# BEP3_RPM_BAR_corrected.net
KiCad netlist of a schematic drawn in EAGLE
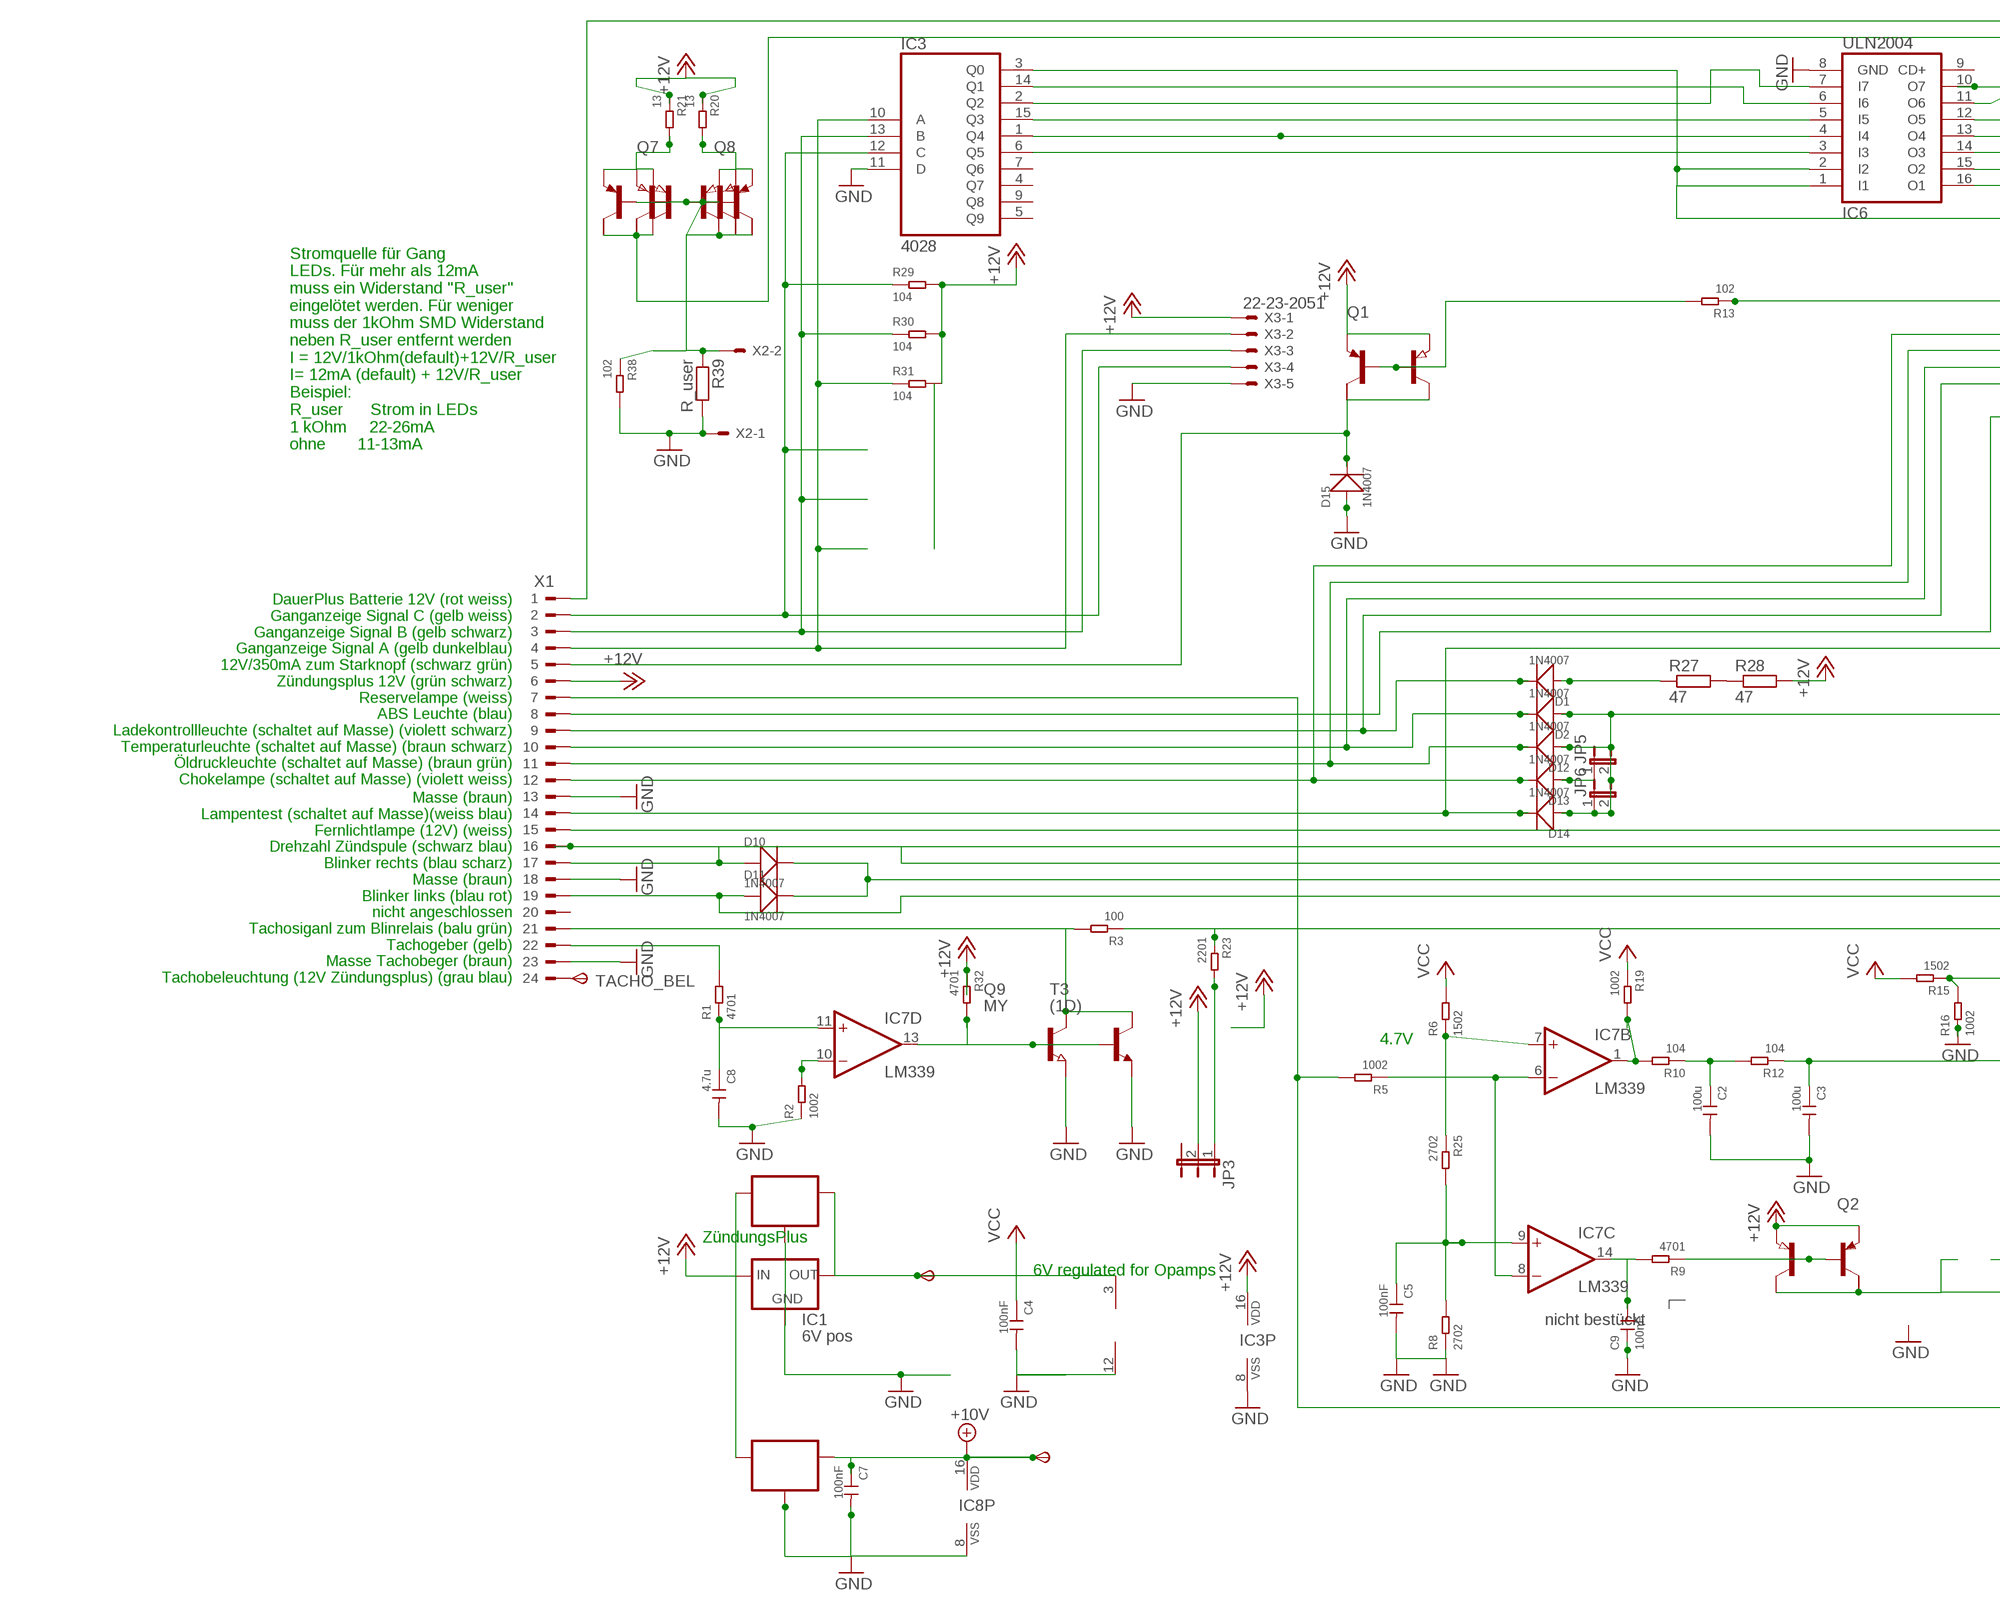
[diagram p0: schematic, sheet 1, part 1 of 2]
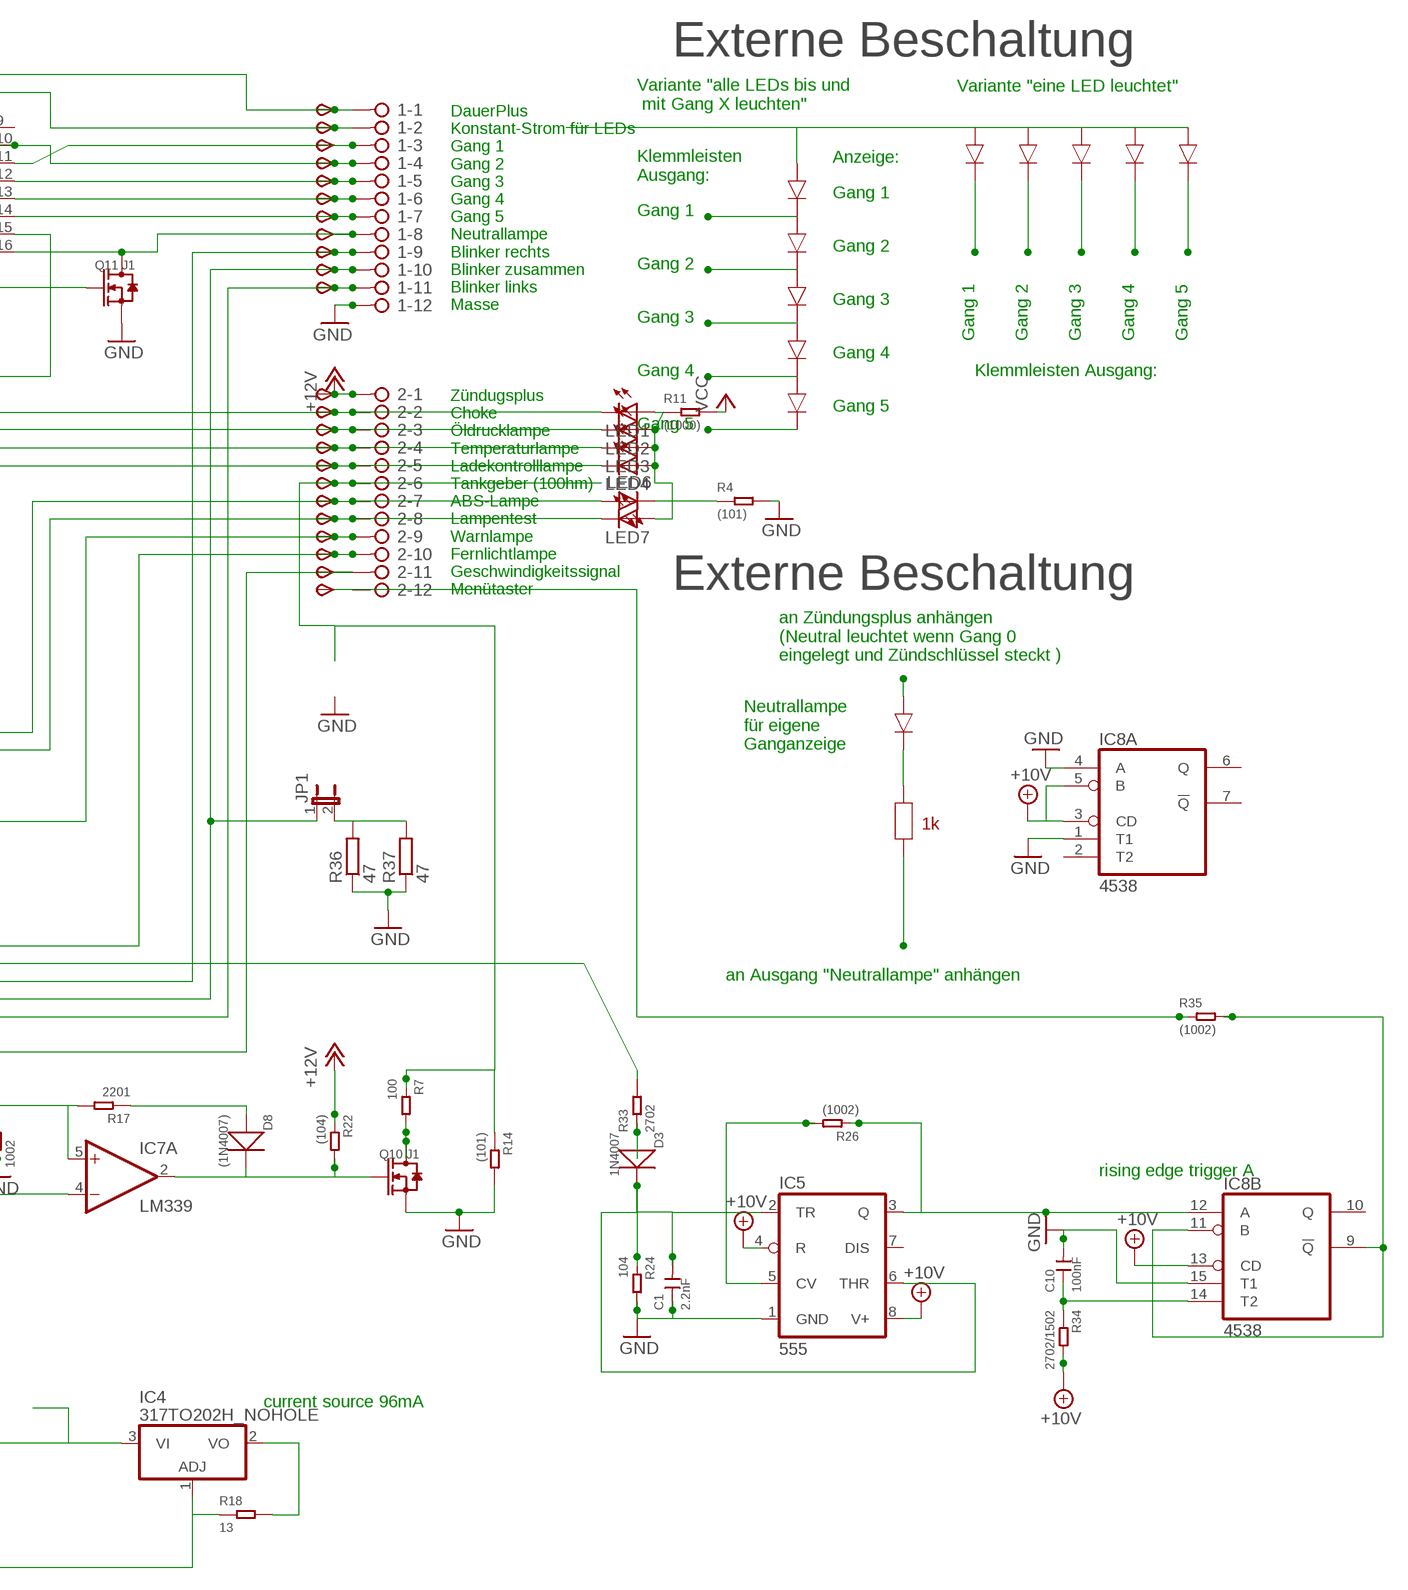
[diagram p1: schematic, sheet 1, part 2 of 2]

(export (version "E")
  (design (tool "Eeschema 10.0.6"))
  (components
    (comp (ref "1")
      (value "2081-1132")
      (footprint "eagle-import:12-PIN")
      (libsource (lib "eagle-import") (part "2081-1132"))
    )
    (comp (ref "2")
      (value "2081-1132")
      (footprint "eagle-import:12-PIN")
      (libsource (lib "eagle-import") (part "2081-1132"))
    )
    (comp (ref "6V")
      (value "TPSB1.8")
      (footprint "eagle-import:B1.8")
      (libsource (lib "eagle-import") (part "TPSB1.8"))
    )
    (comp (ref "10V")
      (value "TPSB1.8")
      (footprint "eagle-import:B1.8")
      (libsource (lib "eagle-import") (part "TPSB1.8"))
    )
    (comp (ref "C1")
      (value "2.2nF")
      (footprint "eagle-import:C0805")
      (fields (field (name "MPN") "CC0805KRX7R9BB104"))
      (libsource (lib "eagle-import") (part "CERAMIC-100NF-50V-10%-X7R(0805)"))
    )
    (comp (ref "C2")
      (value "100u")
      (footprint "eagle-import:C1206")
      (fields (field (name "MPN") "GRM31CR60J107ME39L"))
      (libsource (lib "eagle-import") (part "CERAMIC-100UF-6.3V-20%-X5R(1206)"))
    )
    (comp (ref "C3")
      (value "100u")
      (footprint "eagle-import:C1206")
      (fields (field (name "MPN") "GRM31CR60J107ME39L"))
      (libsource (lib "eagle-import") (part "CERAMIC-100UF-6.3V-20%-X5R(1206)"))
    )
    (comp (ref "C4")
      (value "100nF")
      (footprint "eagle-import:C0805")
      (fields (field (name "MPN") "CC0805KRX7R9BB104"))
      (libsource (lib "eagle-import") (part "CERAMIC-100NF-50V-10%-X7R(0805)"))
    )
    (comp (ref "C5")
      (value "100nF")
      (footprint "eagle-import:C0805")
      (fields (field (name "MPN") "CC0805KRX7R9BB104"))
      (libsource (lib "eagle-import") (part "CERAMIC-100NF-50V-10%-X7R(0805)"))
    )
    (comp (ref "C7")
      (value "100nF")
      (footprint "eagle-import:C0805")
      (fields (field (name "MPN") "CC0805KRX7R9BB104"))
      (libsource (lib "eagle-import") (part "CERAMIC-100NF-50V-10%-X7R(0805)"))
    )
    (comp (ref "C8")
      (value "4.7u")
      (footprint "eagle-import:C0805")
      (fields (field (name "MPN") "CC0805KKX5R8BB475"))
      (libsource (lib "eagle-import") (part "CERAMIC-4.7UF-25V-10%-X5R(0805)"))
    )
    (comp (ref "C9")
      (value "100nF")
      (footprint "eagle-import:C0805")
      (fields (field (name "MPN") "CC0805KRX7R9BB104"))
      (libsource (lib "eagle-import") (part "CERAMIC-100NF-50V-10%-X7R(0805)"))
    )
    (comp (ref "C10")
      (value "100nF")
      (footprint "eagle-import:C0805")
      (fields (field (name "MPN") "CC0805KRX7R9BB104"))
      (libsource (lib "eagle-import") (part "CERAMIC-100NF-50V-10%-X7R(0805)"))
    )
    (comp (ref "D1")
      (value "1N4007")
      (footprint "eagle-import:DO-214AC")
      (libsource (lib "eagle-import") (part "DIODE-GEN-PURPOSE-1KV-1A(DO-214AC)"))
    )
    (comp (ref "D2")
      (value "1N4007")
      (footprint "eagle-import:DO-214AC-1206MOUNT")
      (libsource (lib "eagle-import") (part "DIODE-GEN-PURPOSE-1KV-1A(DO-214AC)DO-214AC/1206"))
    )
    (comp (ref "D3")
      (value "1N4007")
      (footprint "eagle-import:DO-214AC")
      (libsource (lib "eagle-import") (part "DIODE-GEN-PURPOSE-1KV-1A(DO-214AC)"))
    )
    (comp (ref "D8")
      (value "(1N4007)")
      (footprint "eagle-import:DO-214AC-1206MOUNT")
      (libsource (lib "eagle-import") (part "DIODE-GEN-PURPOSE-1KV-1A(DO-214AC)DO-214AC/1206"))
    )
    (comp (ref "D10")
      (value "1N4007")
      (footprint "eagle-import:DO-214AC")
      (libsource (lib "eagle-import") (part "DIODE-GEN-PURPOSE-1KV-1A(DO-214AC)"))
    )
    (comp (ref "D11")
      (value "1N4007")
      (footprint "eagle-import:DO-214AC")
      (libsource (lib "eagle-import") (part "DIODE-GEN-PURPOSE-1KV-1A(DO-214AC)"))
    )
    (comp (ref "D12")
      (value "1N4007")
      (footprint "eagle-import:DO-214AC-1206MOUNT")
      (libsource (lib "eagle-import") (part "DIODE-GEN-PURPOSE-1KV-1A(DO-214AC)DO-214AC/1206"))
    )
    (comp (ref "D13")
      (value "1N4007")
      (footprint "eagle-import:DO-214AC-1206MOUNT")
      (libsource (lib "eagle-import") (part "DIODE-GEN-PURPOSE-1KV-1A(DO-214AC)DO-214AC/1206"))
    )
    (comp (ref "D14")
      (value "1N4007")
      (footprint "eagle-import:DO-214AC-1206MOUNT")
      (libsource (lib "eagle-import") (part "DIODE-GEN-PURPOSE-1KV-1A(DO-214AC)DO-214AC/1206"))
    )
    (comp (ref "D15")
      (value "1N4007")
      (footprint "eagle-import:DO-214AC")
      (libsource (lib "eagle-import") (part "DIODE-GEN-PURPOSE-1KV-1A(DO-214AC)"))
    )
    (comp (ref "IC1")
      (value "6V pos")
      (footprint "eagle-import:78LXX")
      (libsource (lib "eagle-import") (part "v-reg_78LXX"))
    )
    (comp (ref "IC2")
      (value "78LXXSOT89_ROUND")
      (footprint "eagle-import:SOT89_ROUND")
      (libsource (lib "eagle-import") (part "78LXXSOT89_ROUND"))
    )
    (comp (ref "IC3")
      (value "4028")
      (footprint "eagle-import:SO16")
      (libsource (lib "eagle-import") (part "4028D"))
    )
    (comp (ref "IC4")
      (value "317TO202H_NOHOLE")
      (footprint "eagle-import:TO220H_NOHOLE")
      (libsource (lib "eagle-import") (part "317TO202H_NOHOLE"))
    )
    (comp (ref "IC5")
      (value "555")
      (footprint "eagle-import:SO08")
      (libsource (lib "eagle-import") (part "555DNE"))
    )
    (comp (ref "IC6")
      (value "ULN2004")
      (footprint "eagle-import:SO16")
      (libsource (lib "eagle-import") (part "ULN2004AD"))
    )
    (comp (ref "IC7")
      (value "LM339")
      (footprint "eagle-import:SO14")
      (libsource (lib "eagle-import") (part "LM339D"))
    )
    (comp (ref "IC8")
      (value "4538")
      (footprint "eagle-import:SO16")
      (libsource (lib "eagle-import") (part "4538D"))
    )
    (comp (ref "IC9")
      (value "78LXXSOT89_ROUND")
      (footprint "eagle-import:SOT89_ROUND")
      (libsource (lib "eagle-import") (part "78LXXSOT89_ROUND"))
    )
    (comp (ref "JP1")
      (value "JP1E")
      (footprint "eagle-import:JP1")
      (libsource (lib "eagle-import") (part "JP1E"))
    )
    (comp (ref "JP3")
      (value "JP2E")
      (footprint "eagle-import:JP2")
      (libsource (lib "eagle-import") (part "JP2E"))
    )
    (comp (ref "JP5")
      (value "JP1E")
      (footprint "eagle-import:JP1")
      (libsource (lib "eagle-import") (part "JP1E"))
    )
    (comp (ref "JP6")
      (value "JP1E")
      (footprint "eagle-import:JP1")
      (libsource (lib "eagle-import") (part "JP1E"))
    )
    (comp (ref "LED1")
      (value "LEDLD260")
      (footprint "eagle-import:LD260")
      (libsource (lib "eagle-import") (part "LEDLD260"))
    )
    (comp (ref "LED2")
      (value "LEDLD260")
      (footprint "eagle-import:LD260")
      (libsource (lib "eagle-import") (part "LEDLD260"))
    )
    (comp (ref "LED3")
      (value "LEDLD260")
      (footprint "eagle-import:LD260")
      (libsource (lib "eagle-import") (part "LEDLD260"))
    )
    (comp (ref "LED4")
      (value "LEDLD260")
      (footprint "eagle-import:LD260")
      (libsource (lib "eagle-import") (part "LEDLD260"))
    )
    (comp (ref "LED6")
      (value "LEDLD260")
      (footprint "eagle-import:LD260")
      (libsource (lib "eagle-import") (part "LEDLD260"))
    )
    (comp (ref "LED7")
      (value "LEDLD260")
      (footprint "eagle-import:LD260")
      (libsource (lib "eagle-import") (part "LEDLD260"))
    )
    (comp (ref "Q1")
      (value "PNP-TRANSISTOR_SOT89")
      (footprint "eagle-import:SOT89")
      (libsource (lib "eagle-import") (part "PNP-TRANSISTOR_SOT89"))
    )
    (comp (ref "Q2")
      (value "PNP-TRANSISTOR_SOT89")
      (footprint "eagle-import:SOT89")
      (libsource (lib "eagle-import") (part "PNP-TRANSISTOR_SOT89"))
    )
    (comp (ref "Q3")
      (value "AH-16")
      (footprint "eagle-import:SOT223")
      (libsource (lib "eagle-import") (part "BCP53T1"))
    )
    (comp (ref "Q4")
      (value "(AH-16)")
      (footprint "eagle-import:SOT223")
      (libsource (lib "eagle-import") (part "BCP53T1"))
    )
    (comp (ref "Q5")
      (value "(AH-16)")
      (footprint "eagle-import:SOT223")
      (libsource (lib "eagle-import") (part "BCP53T1"))
    )
    (comp (ref "Q6")
      (value "(AH-16)")
      (footprint "eagle-import:SOT223")
      (libsource (lib "eagle-import") (part "BCP53T1"))
    )
    (comp (ref "Q7")
      (value "PNP-TRANSISTOR_SOT89")
      (footprint "eagle-import:SOT89")
      (libsource (lib "eagle-import") (part "PNP-TRANSISTOR_SOT89"))
    )
    (comp (ref "Q8")
      (value "PNP-TRANSISTOR_SOT89")
      (footprint "eagle-import:SOT89")
      (libsource (lib "eagle-import") (part "PNP-TRANSISTOR_SOT89"))
    )
    (comp (ref "Q9")
      (value "MY")
      (footprint "eagle-import:SOT89")
      (libsource (lib "eagle-import") (part "NPN-TRANSISTOR_SOT89"))
    )
    (comp (ref "Q10")
      (value "J1")
      (footprint "eagle-import:SOT-23")
      (fields (field (name "MPN") "BSS138W-7-F"))
      (libsource (lib "eagle-import") (part "SMD-MOSFET-N-CH-50V-200MA-BSS138W-7-F(SOT-23)"))
    )
    (comp (ref "Q11")
      (value "J1")
      (footprint "eagle-import:SOT-23")
      (fields (field (name "MPN") "BSS138W-7-F"))
      (libsource (lib "eagle-import") (part "SMD-MOSFET-N-CH-50V-200MA-BSS138W-7-F(SOT-23)"))
    )
    (comp (ref "R1")
      (value "4701")
      (footprint "eagle-import:R0805")
      (fields (field (name "MPN") "RC0805JR-074K7L"))
      (libsource (lib "eagle-import") (part "SMD-RES-4.7K-5%-1/8W(0805)"))
    )
    (comp (ref "R2")
      (value "1002")
      (footprint "eagle-import:R0805")
      (fields (field (name "MPN") "RC0805FR-0710KL"))
      (libsource (lib "eagle-import") (part "SMD-RES-10K-1%-1/8W(0805)"))
    )
    (comp (ref "R3")
      (value "100")
      (footprint "eagle-import:R0805")
      (fields (field (name "MPN") "RC0805JR-07220RL"))
      (libsource (lib "eagle-import") (part "SMD-RES-220R-5%-1/8W(0805)"))
    )
    (comp (ref "R4")
      (value "(101)")
      (footprint "eagle-import:R0805")
      (fields (field (name "MPN") "RC0805JR-07100RL"))
      (libsource (lib "eagle-import") (part "SMD-RES-100R-5%-1/8W(0805)"))
    )
    (comp (ref "R5")
      (value "1002")
      (footprint "eagle-import:R0805")
      (fields (field (name "MPN") "RC0805FR-0710KL"))
      (libsource (lib "eagle-import") (part "SMD-RES-10K-1%-1/8W(0805)"))
    )
    (comp (ref "R6")
      (value "1502")
      (footprint "eagle-import:R0805")
      (fields (field (name "MPN") "RC0805FR-0710KL"))
      (libsource (lib "eagle-import") (part "SMD-RES-10K-1%-1/8W(0805)"))
    )
    (comp (ref "R7")
      (value "100")
      (footprint "eagle-import:R0805")
      (fields (field (name "MPN") "RC0805JR-072K2L"))
      (libsource (lib "eagle-import") (part "SMD-RES-2.2K-5%-1/8W(0805)"))
    )
    (comp (ref "R8")
      (value "2702")
      (footprint "eagle-import:R0805")
      (fields (field (name "MPN") "RC0805JR-074K7L"))
      (libsource (lib "eagle-import") (part "SMD-RES-4.7K-5%-1/8W(0805)"))
    )
    (comp (ref "R9")
      (value "4701")
      (footprint "eagle-import:R0805")
      (fields (field (name "MPN") "RC0805JR-074K7L"))
      (libsource (lib "eagle-import") (part "SMD-RES-4.7K-5%-1/8W(0805)"))
    )
    (comp (ref "R10")
      (value "104")
      (footprint "eagle-import:R0805")
      (fields (field (name "MPN") "RC0805FR-0710KL"))
      (libsource (lib "eagle-import") (part "SMD-RES-10K-1%-1/8W(0805)"))
    )
    (comp (ref "R11")
      (value "(1000)")
      (footprint "eagle-import:R0805")
      (fields (field (name "MPN") "RC0805JR-07100RL"))
      (libsource (lib "eagle-import") (part "SMD-RES-100R-5%-1/8W(0805)"))
    )
    (comp (ref "R12")
      (value "104")
      (footprint "eagle-import:R0805")
      (fields (field (name "MPN") "RC0805FR-0710KL"))
      (libsource (lib "eagle-import") (part "SMD-RES-10K-1%-1/8W(0805)"))
    )
    (comp (ref "R13")
      (value "102")
      (footprint "eagle-import:R0805")
      (fields (field (name "MPN") "RC0805JR-071KL"))
      (libsource (lib "eagle-import") (part "SMD-RES-1K-5%-1/8W(0805)"))
    )
    (comp (ref "R14")
      (value "(101)")
      (footprint "eagle-import:R0805")
      (fields (field (name "MPN") "RC0805JR-072K2L"))
      (libsource (lib "eagle-import") (part "SMD-RES-2.2K-5%-1/8W(0805)"))
    )
    (comp (ref "R15")
      (value "1502")
      (footprint "eagle-import:R0805")
      (fields (field (name "MPN") "RC0805FR-0710KL"))
      (libsource (lib "eagle-import") (part "SMD-RES-10K-1%-1/8W(0805)"))
    )
    (comp (ref "R16")
      (value "1002")
      (footprint "eagle-import:R0805")
      (fields (field (name "MPN") "RC0805FR-0710KL"))
      (libsource (lib "eagle-import") (part "SMD-RES-10K-1%-1/8W(0805)"))
    )
    (comp (ref "R17")
      (value "2201")
      (footprint "eagle-import:R0805")
      (fields (field (name "MPN") "RC0805JR-072K2L"))
      (libsource (lib "eagle-import") (part "SMD-RES-2.2K-5%-1/8W(0805)"))
    )
    (comp (ref "R18")
      (value "13")
      (footprint "eagle-import:R1206")
      (fields (field (name "MPN") "RC1206JR-0713RL"))
      (libsource (lib "eagle-import") (part "SMD-RES-13R-5%-1/4W(1206)"))
    )
    (comp (ref "R19")
      (value "1002")
      (footprint "eagle-import:R0805")
      (fields (field (name "MPN") "RC0805FR-0710KL"))
      (libsource (lib "eagle-import") (part "SMD-RES-10K-1%-1/8W(0805)"))
    )
    (comp (ref "R20")
      (value "13")
      (footprint "eagle-import:R1206")
      (fields (field (name "MPN") "RC1206JR-0713RL"))
      (libsource (lib "eagle-import") (part "SMD-RES-13R-5%-1/4W(1206)"))
    )
    (comp (ref "R21")
      (value "13")
      (footprint "eagle-import:R1206")
      (fields (field (name "MPN") "RC1206JR-0713RL"))
      (libsource (lib "eagle-import") (part "SMD-RES-13R-5%-1/4W(1206)"))
    )
    (comp (ref "R22")
      (value "(104)")
      (footprint "eagle-import:R0805")
      (fields (field (name "MPN") "RC0805FR-0710KL"))
      (libsource (lib "eagle-import") (part "SMD-RES-10K-1%-1/8W(0805)"))
    )
    (comp (ref "R23")
      (value "2201")
      (footprint "eagle-import:R0805")
      (fields (field (name "MPN") "RC0805JR-072K2L"))
      (libsource (lib "eagle-import") (part "SMD-RES-2.2K-5%-1/8W(0805)"))
    )
    (comp (ref "R24")
      (value "104")
      (footprint "eagle-import:R0805")
      (fields (field (name "MPN") "RC0805FR-0710KL"))
      (libsource (lib "eagle-import") (part "SMD-RES-10K-1%-1/8W(0805)"))
    )
    (comp (ref "R25")
      (value "2702")
      (footprint "eagle-import:R0805")
      (fields (field (name "MPN") "RC0805JR-074K7L"))
      (libsource (lib "eagle-import") (part "SMD-RES-4.7K-5%-1/8W(0805)"))
    )
    (comp (ref "R26")
      (value "(1002)")
      (footprint "eagle-import:R0805")
      (fields (field (name "MPN") "RC0805FR-0710KL"))
      (libsource (lib "eagle-import") (part "SMD-RES-10K-1%-1/8W(0805)"))
    )
    (comp (ref "R27")
      (value "47")
      (footprint "eagle-import:V235_17_1MM")
      (libsource (lib "eagle-import") (part "R-EU_V235/17_1MM"))
    )
    (comp (ref "R28")
      (value "47")
      (footprint "eagle-import:V235_17_1MM")
      (libsource (lib "eagle-import") (part "R-EU_V235/17_1MM"))
    )
    (comp (ref "R29")
      (value "104")
      (footprint "eagle-import:R0805")
      (fields (field (name "MPN") "RC0805FR-0710KL"))
      (libsource (lib "eagle-import") (part "SMD-RES-10K-1%-1/8W(0805)"))
    )
    (comp (ref "R30")
      (value "104")
      (footprint "eagle-import:R0805")
      (fields (field (name "MPN") "RC0805FR-0710KL"))
      (libsource (lib "eagle-import") (part "SMD-RES-10K-1%-1/8W(0805)"))
    )
    (comp (ref "R31")
      (value "104")
      (footprint "eagle-import:R0805")
      (fields (field (name "MPN") "RC0805FR-0710KL"))
      (libsource (lib "eagle-import") (part "SMD-RES-10K-1%-1/8W(0805)"))
    )
    (comp (ref "R32")
      (value "4701")
      (footprint "eagle-import:R0805")
      (fields (field (name "MPN") "RC0805JR-074K7L"))
      (libsource (lib "eagle-import") (part "SMD-RES-4.7K-5%-1/8W(0805)"))
    )
    (comp (ref "R33")
      (value "2702")
      (footprint "eagle-import:R0805")
      (fields (field (name "MPN") "RC0805FR-0710KL"))
      (libsource (lib "eagle-import") (part "SMD-RES-10K-1%-1/8W(0805)"))
    )
    (comp (ref "R34")
      (value "2702/1502")
      (footprint "eagle-import:R0805")
      (fields (field (name "MPN") "RC0805JR-074K7L"))
      (libsource (lib "eagle-import") (part "SMD-RES-4.7K-5%-1/8W(0805)"))
    )
    (comp (ref "R35")
      (value "(1002)")
      (footprint "eagle-import:R0805")
      (fields (field (name "MPN") "RC0805JR-074K7L"))
      (libsource (lib "eagle-import") (part "SMD-RES-4.7K-5%-1/8W(0805)"))
    )
    (comp (ref "R36")
      (value "47")
      (footprint "eagle-import:V235_17_1MM")
      (libsource (lib "eagle-import") (part "R-EU_V235/17_1MM"))
    )
    (comp (ref "R37")
      (value "47")
      (footprint "eagle-import:V235_17_1MM")
      (libsource (lib "eagle-import") (part "R-EU_V235/17_1MM"))
    )
    (comp (ref "R38")
      (value "102")
      (footprint "eagle-import:R0805")
      (fields (field (name "MPN") "RC0805JR-071KL"))
      (libsource (lib "eagle-import") (part "SMD-RES-1K-5%-1/8W(0805)"))
    )
    (comp (ref "R39")
      (value "R_user")
      (footprint "eagle-import:R0805")
      (libsource (lib "eagle-import") (part "R-EU_R0805"))
    )
    (comp (ref "T1")
      (value "PNP2SM8")
      (footprint "eagle-import:SM8")
      (libsource (lib "eagle-import") (part "PNP2SM8"))
    )
    (comp (ref "T3")
      (value "(1D)")
      (footprint "eagle-import:SOT23-BEC")
      (libsource (lib "eagle-import") (part "-NPN-SOT23-BECMMBTA42LT1"))
    )
    (comp (ref "TACHO_BEL")
      (value "TPSP1_1MM")
      (footprint "eagle-import:P1_1.0MM")
      (libsource (lib "eagle-import") (part "TPSP1_1MM"))
    )
    (comp (ref "TP1")
      (value "TPSB1.8")
      (footprint "eagle-import:B1.8")
      (libsource (lib "eagle-import") (part "TPSB1.8"))
    )
    (comp (ref "TP2")
      (value "TPSB1.8")
      (footprint "eagle-import:B1.8")
      (libsource (lib "eagle-import") (part "TPSB1.8"))
    )
    (comp (ref "TP3")
      (value "TPSB1.8")
      (footprint "eagle-import:B1.8")
      (libsource (lib "eagle-import") (part "TPSB1.8"))
    )
    (comp (ref "TP4")
      (value "TPSB1.8")
      (footprint "eagle-import:B1.8")
      (libsource (lib "eagle-import") (part "TPSB1.8"))
    )
    (comp (ref "TP5")
      (value "TPSB1.8")
      (footprint "eagle-import:B1.8")
      (libsource (lib "eagle-import") (part "TPSB1.8"))
    )
    (comp (ref "TP6")
      (value "TPSB1.8")
      (footprint "eagle-import:B1.8")
      (libsource (lib "eagle-import") (part "TPSB1.8"))
    )
    (comp (ref "TP7")
      (value "TPSB1.8")
      (footprint "eagle-import:B1.8")
      (libsource (lib "eagle-import") (part "TPSB1.8"))
    )
    (comp (ref "TP8")
      (value "TPSB1.8")
      (footprint "eagle-import:B1.8")
      (libsource (lib "eagle-import") (part "TPSB1.8"))
    )
    (comp (ref "TP9")
      (value "TPSB1.8")
      (footprint "eagle-import:B1.8")
      (libsource (lib "eagle-import") (part "TPSB1.8"))
    )
    (comp (ref "TP10")
      (value "TPSB1.8")
      (footprint "eagle-import:B1.8")
      (libsource (lib "eagle-import") (part "TPSB1.8"))
    )
    (comp (ref "TP11")
      (value "TPSB1.8")
      (footprint "eagle-import:B1.8")
      (libsource (lib "eagle-import") (part "TPSB1.8"))
    )
    (comp (ref "TP12")
      (value "TPSB1.8")
      (footprint "eagle-import:B1.8")
      (libsource (lib "eagle-import") (part "TPSB1.8"))
    )
    (comp (ref "TP13")
      (value "TPSB1,27")
      (footprint "eagle-import:B1,27")
      (libsource (lib "eagle-import") (part "TPSB1,27"))
    )
    (comp (ref "TP16")
      (value "TPSB1.8")
      (footprint "eagle-import:B1.8")
      (libsource (lib "eagle-import") (part "TPSB1.8"))
    )
    (comp (ref "TP17")
      (value "TPSB1.8")
      (footprint "eagle-import:B1.8")
      (libsource (lib "eagle-import") (part "TPSB1.8"))
    )
    (comp (ref "TP18")
      (value "TPSB1.8")
      (footprint "eagle-import:B1.8")
      (libsource (lib "eagle-import") (part "TPSB1.8"))
    )
    (comp (ref "TP19")
      (value "TPSB1.8")
      (footprint "eagle-import:B1.8")
      (libsource (lib "eagle-import") (part "TPSB1.8"))
    )
    (comp (ref "TP21")
      (value "TPSB1.8")
      (footprint "eagle-import:B1.8")
      (libsource (lib "eagle-import") (part "TPSB1.8"))
    )
    (comp (ref "TP22")
      (value "TPSB1.8")
      (footprint "eagle-import:B1.8")
      (libsource (lib "eagle-import") (part "TPSB1.8"))
    )
    (comp (ref "TP23")
      (value "TPSB1.8")
      (footprint "eagle-import:B1.8")
      (libsource (lib "eagle-import") (part "TPSB1.8"))
    )
    (comp (ref "TP24")
      (value "TPSB1,27")
      (footprint "eagle-import:B1,27")
      (libsource (lib "eagle-import") (part "TPSB1,27"))
    )
    (comp (ref "TP25")
      (value "TPSB1.8")
      (footprint "eagle-import:B1.8")
      (libsource (lib "eagle-import") (part "TPSB1.8"))
    )
    (comp (ref "TP26")
      (value "TPSB1.8")
      (footprint "eagle-import:B1.8")
      (libsource (lib "eagle-import") (part "TPSB1.8"))
    )
    (comp (ref "X1")
      (value "CON_BMWV2")
      (footprint "eagle-import:24-PIN_V2")
      (libsource (lib "eagle-import") (part "CON_BMWV2"))
    )
    (comp (ref "X2")
      (value "22-23-2021")
      (footprint "eagle-import:22-23-2021")
      (fields (field (name "MF") "MOLEX"))
      (libsource (lib "eagle-import") (part "22-23-2021"))
    )
    (comp (ref "X3")
      (value "22-23-2051")
      (footprint "eagle-import:22-23-2051")
      (fields (field (name "MF") "MOLEX"))
      (libsource (lib "eagle-import") (part "22-23-2051"))
    )
  )
  (nets
    (net (code "1") (name "+10V") (class "Default")
      (node (ref "10V") (pin "TP") (pinfunction "PP_TP") (pintype "input"))
      (node (ref "C7") (pin "1") (pinfunction "1_1") (pintype "passive"))
      (node (ref "IC5") (pin "4") (pinfunction "R_4") (pintype "input"))
      (node (ref "IC5") (pin "8") (pinfunction "V+_8") (pintype "power_in"))
      (node (ref "IC8") (pin "13") (pinfunction "CD_13") (pintype "input"))
      (node (ref "IC8") (pin "16") (pinfunction "VDD_16") (pintype "power_in"))
      (node (ref "IC8") (pin "3") (pinfunction "CD_3") (pintype "input"))
      (node (ref "IC8") (pin "5") (pinfunction "B_5") (pintype "input"))
      (node (ref "IC9") (pin "1") (pinfunction "OUT_1") (pintype "passive"))
      (node (ref "R34") (pin "2") (pinfunction "2_2") (pintype "passive"))
    )
    (net (code "2") (name "+12V") (class "Default")
      (node (ref "2") (pin "1") (pinfunction "KL_1") (pintype "passive"))
      (node (ref "IC1") (pin "IN") (pinfunction "IN_IN") (pintype "input"))
      (node (ref "IC2") (pin "3") (pinfunction "IN_3") (pintype "input"))
      (node (ref "IC3") (pin "16") (pinfunction "VDD_16") (pintype "power_in"))
      (node (ref "IC9") (pin "3") (pinfunction "IN_3") (pintype "input"))
      (node (ref "JP3") (pin "2") (pinfunction "2_2") (pintype "passive"))
      (node (ref "Q1") (pin "3") (pinfunction "E_3") (pintype "passive"))
      (node (ref "Q2") (pin "3") (pinfunction "E_3") (pintype "passive"))
      (node (ref "Q3") (pin "3") (pinfunction "E_3") (pintype "passive"))
      (node (ref "Q4") (pin "3") (pinfunction "E_3") (pintype "passive"))
      (node (ref "R20") (pin "1") (pinfunction "1_1") (pintype "passive"))
      (node (ref "R21") (pin "1") (pinfunction "1_1") (pintype "passive"))
      (node (ref "R22") (pin "1") (pinfunction "1_1") (pintype "passive"))
      (node (ref "R28") (pin "2") (pinfunction "2_2") (pintype "passive"))
      (node (ref "R29") (pin "2") (pinfunction "2_2") (pintype "passive"))
      (node (ref "R30") (pin "2") (pinfunction "2_2") (pintype "passive"))
      (node (ref "R31") (pin "2") (pinfunction "2_2") (pintype "passive"))
      (node (ref "R32") (pin "1") (pinfunction "1_1") (pintype "passive"))
      (node (ref "TP12") (pin "TP") (pinfunction "PP_TP") (pintype "input"))
      (node (ref "X1") (pin "6") (pinfunction "6_6") (pintype "passive"))
      (node (ref "X3") (pin "1") (pinfunction "S_1") (pintype "passive"))
    )
    (net (code "3") (name "GND") (class "Default")
      (node (ref "1") (pin "12") (pinfunction "KL_12") (pintype "passive"))
      (node (ref "C1") (pin "1") (pinfunction "1_1") (pintype "passive"))
      (node (ref "C10") (pin "2") (pinfunction "2_2") (pintype "passive"))
      (node (ref "C2") (pin "2") (pinfunction "2_2") (pintype "passive"))
      (node (ref "C3") (pin "2") (pinfunction "2_2") (pintype "passive"))
      (node (ref "C4") (pin "2") (pinfunction "2_2") (pintype "passive"))
      (node (ref "C5") (pin "2") (pinfunction "2_2") (pintype "passive"))
      (node (ref "C7") (pin "2") (pinfunction "2_2") (pintype "passive"))
      (node (ref "C8") (pin "2") (pinfunction "2_2") (pintype "passive"))
      (node (ref "C9") (pin "1") (pinfunction "1_1") (pintype "passive"))
      (node (ref "D15") (pin "1") (pinfunction "+_1") (pintype "passive"))
      (node (ref "IC1") (pin "GND") (pinfunction "GND_GND") (pintype "input"))
      (node (ref "IC2") (pin "2") (pinfunction "GND_2") (pintype "input"))
      (node (ref "IC2") (pin "2@1") (pinfunction "GND_2@1") (pintype "input"))
      (node (ref "IC3") (pin "11") (pinfunction "D_11") (pintype "input"))
      (node (ref "IC3") (pin "8") (pinfunction "VSS_8") (pintype "power_in"))
      (node (ref "IC5") (pin "1") (pinfunction "GND_1") (pintype "power_in"))
      (node (ref "IC6") (pin "8") (pinfunction "GND_8") (pintype "power_in"))
      (node (ref "IC7") (pin "12") (pinfunction "GND_12") (pintype "power_in"))
      (node (ref "IC8") (pin "1") (pinfunction "T1_1") (pintype "input"))
      (node (ref "IC8") (pin "15") (pinfunction "T1_15") (pintype "input"))
      (node (ref "IC8") (pin "4") (pinfunction "A_4") (pintype "input"))
      (node (ref "IC8") (pin "8") (pinfunction "VSS_8") (pintype "power_in"))
      (node (ref "IC9") (pin "2") (pinfunction "GND_2") (pintype "input"))
      (node (ref "IC9") (pin "2@1") (pinfunction "GND_2@1") (pintype "input"))
      (node (ref "Q10") (pin "2") (pinfunction "S_2") (pintype "passive"))
      (node (ref "Q11") (pin "2") (pinfunction "S_2") (pintype "passive"))
      (node (ref "Q9") (pin "3") (pinfunction "E_3") (pintype "passive"))
      (node (ref "R14") (pin "2") (pinfunction "2_2") (pintype "passive"))
      (node (ref "R16") (pin "1") (pinfunction "1_1") (pintype "passive"))
      (node (ref "R2") (pin "1") (pinfunction "1_1") (pintype "passive"))
      (node (ref "R24") (pin "2") (pinfunction "2_2") (pintype "passive"))
      (node (ref "R36") (pin "1") (pinfunction "1_1") (pintype "passive"))
      (node (ref "R37") (pin "1") (pinfunction "1_1") (pintype "passive"))
      (node (ref "R38") (pin "2") (pinfunction "2_2") (pintype "passive"))
      (node (ref "R39") (pin "2") (pinfunction "2_2") (pintype "passive"))
      (node (ref "R4") (pin "2") (pinfunction "2_2") (pintype "passive"))
      (node (ref "R8") (pin "1") (pinfunction "1_1") (pintype "passive"))
      (node (ref "T3") (pin "E") (pinfunction "E_E") (pintype "passive"))
      (node (ref "X1") (pin "13") (pinfunction "13_13") (pintype "passive"))
      (node (ref "X1") (pin "18") (pinfunction "18_18") (pintype "passive"))
      (node (ref "X1") (pin "23") (pinfunction "23_23") (pintype "passive"))
      (node (ref "X2") (pin "1") (pinfunction "S_1") (pintype "passive"))
      (node (ref "X3") (pin "5") (pinfunction "S_5") (pintype "passive"))
    )
    (net (code "4") (name "Net-(1A-KL)") (class "Default")
      (node (ref "1") (pin "1") (pinfunction "KL_1") (pintype "passive"))
      (node (ref "TP1") (pin "TP") (pinfunction "PP_TP") (pintype "input"))
      (node (ref "X1") (pin "1") (pinfunction "1_1") (pintype "passive"))
    )
    (net (code "5") (name "Net-(1B-KL)") (class "Default")
      (node (ref "1") (pin "10") (pinfunction "KL_10") (pintype "passive"))
      (node (ref "D10") (pin "2") (pinfunction "-_2") (pintype "passive"))
      (node (ref "D11") (pin "2") (pinfunction "-_2") (pintype "passive"))
      (node (ref "JP1") (pin "1") (pinfunction "1_1") (pintype "passive"))
      (node (ref "TP10") (pin "TP") (pinfunction "PP_TP") (pintype "input"))
    )
    (net (code "6") (name "Net-(1C-KL)") (class "Default")
      (node (ref "1") (pin "11") (pinfunction "KL_11") (pintype "passive"))
      (node (ref "D11") (pin "1") (pinfunction "+_1") (pintype "passive"))
      (node (ref "TP11") (pin "TP") (pinfunction "PP_TP") (pintype "input"))
      (node (ref "X1") (pin "19") (pinfunction "19_19") (pintype "passive"))
    )
    (net (code "7") (name "Net-(1E-KL)") (class "Default")
      (node (ref "1") (pin "2") (pinfunction "KL_2") (pintype "passive"))
      (node (ref "Q5") (pin "2") (pinfunction "C_2") (pintype "passive"))
      (node (ref "Q8") (pin "2") (pinfunction "C_2") (pintype "passive"))
      (node (ref "T1") (pin "8") (pinfunction "C1_8") (pintype "passive"))
      (node (ref "TP2") (pin "TP") (pinfunction "PP_TP") (pintype "input"))
    )
    (net (code "8") (name "Net-(1F-KL)") (class "Default")
      (node (ref "1") (pin "3") (pinfunction "KL_3") (pintype "passive"))
      (node (ref "IC6") (pin "11") (pinfunction "O6_11") (pintype "open_collector"))
      (node (ref "TP3") (pin "TP") (pinfunction "PP_TP") (pintype "input"))
    )
    (net (code "9") (name "Net-(1G-KL)") (class "Default")
      (node (ref "1") (pin "4") (pinfunction "KL_4") (pintype "passive"))
      (node (ref "IC6") (pin "10") (pinfunction "O7_10") (pintype "open_collector"))
      (node (ref "TP4") (pin "TP") (pinfunction "PP_TP") (pintype "input"))
    )
    (net (code "10") (name "Net-(1H-KL)") (class "Default")
      (node (ref "1") (pin "5") (pinfunction "KL_5") (pintype "passive"))
      (node (ref "IC6") (pin "12") (pinfunction "O5_12") (pintype "open_collector"))
      (node (ref "TP5") (pin "TP") (pinfunction "PP_TP") (pintype "input"))
    )
    (net (code "11") (name "Net-(1I-KL)") (class "Default")
      (node (ref "1") (pin "6") (pinfunction "KL_6") (pintype "passive"))
      (node (ref "IC6") (pin "13") (pinfunction "O4_13") (pintype "open_collector"))
      (node (ref "TP6") (pin "TP") (pinfunction "PP_TP") (pintype "input"))
    )
    (net (code "12") (name "Net-(1J-KL)") (class "Default")
      (node (ref "1") (pin "7") (pinfunction "KL_7") (pintype "passive"))
      (node (ref "IC6") (pin "14") (pinfunction "O3_14") (pintype "open_collector"))
      (node (ref "TP7") (pin "TP") (pinfunction "PP_TP") (pintype "input"))
    )
    (net (code "13") (name "Net-(1K-KL)") (class "Default")
      (node (ref "1") (pin "8") (pinfunction "KL_8") (pintype "passive"))
      (node (ref "IC6") (pin "16") (pinfunction "O1_16") (pintype "open_collector"))
      (node (ref "Q11") (pin "3") (pinfunction "D_3") (pintype "passive"))
      (node (ref "TP8") (pin "TP") (pinfunction "PP_TP") (pintype "input"))
    )
    (net (code "14") (name "Net-(1L-KL)") (class "Default")
      (node (ref "1") (pin "9") (pinfunction "KL_9") (pintype "passive"))
      (node (ref "D10") (pin "1") (pinfunction "+_1") (pintype "passive"))
      (node (ref "TP9") (pin "TP") (pinfunction "PP_TP") (pintype "input"))
      (node (ref "X1") (pin "17") (pinfunction "17_17") (pintype "passive"))
    )
    (net (code "15") (name "Net-(2B-KL)") (class "Default")
      (node (ref "2") (pin "10") (pinfunction "KL_10") (pintype "passive"))
      (node (ref "TP25") (pin "TP") (pinfunction "PP_TP") (pintype "input"))
      (node (ref "X1") (pin "15") (pinfunction "15_15") (pintype "passive"))
    )
    (net (code "16") (name "Net-(2C-KL)") (class "Default")
      (node (ref "2") (pin "11") (pinfunction "KL_11") (pintype "passive"))
      (node (ref "R23") (pin "1") (pinfunction "1_1") (pintype "passive"))
      (node (ref "R3") (pin "1") (pinfunction "1_1") (pintype "passive"))
      (node (ref "TP26") (pin "TP") (pinfunction "PP_TP") (pintype "input"))
    )
    (net (code "17") (name "Net-(2D-KL)") (class "Default")
      (node (ref "2") (pin "12") (pinfunction "KL_12") (pintype "passive"))
      (node (ref "R35") (pin "1") (pinfunction "1_1") (pintype "passive"))
      (node (ref "TP13") (pin "TP") (pinfunction "PP_TP") (pintype "input"))
    )
    (net (code "18") (name "Net-(2E-KL)") (class "Default")
      (node (ref "2") (pin "2") (pinfunction "KL_2") (pintype "passive"))
      (node (ref "D13") (pin "2") (pinfunction "-_2") (pintype "passive"))
      (node (ref "LED1") (pin "K") (pinfunction "C_K") (pintype "passive"))
      (node (ref "TP16") (pin "TP") (pinfunction "PP_TP") (pintype "input"))
      (node (ref "X1") (pin "12") (pinfunction "12_12") (pintype "passive"))
    )
    (net (code "19") (name "Net-(2F-KL)") (class "Default")
      (node (ref "2") (pin "3") (pinfunction "KL_3") (pintype "passive"))
      (node (ref "D12") (pin "2") (pinfunction "-_2") (pintype "passive"))
      (node (ref "LED2") (pin "K") (pinfunction "C_K") (pintype "passive"))
      (node (ref "TP17") (pin "TP") (pinfunction "PP_TP") (pintype "input"))
      (node (ref "X1") (pin "11") (pinfunction "11_11") (pintype "passive"))
    )
    (net (code "20") (name "Net-(2G-KL)") (class "Default")
      (node (ref "2") (pin "4") (pinfunction "KL_4") (pintype "passive"))
      (node (ref "D2") (pin "2") (pinfunction "-_2") (pintype "passive"))
      (node (ref "LED3") (pin "K") (pinfunction "C_K") (pintype "passive"))
      (node (ref "TP18") (pin "TP") (pinfunction "PP_TP") (pintype "input"))
      (node (ref "X1") (pin "10") (pinfunction "10_10") (pintype "passive"))
    )
    (net (code "21") (name "Net-(2H-KL)") (class "Default")
      (node (ref "2") (pin "5") (pinfunction "KL_5") (pintype "passive"))
      (node (ref "D1") (pin "2") (pinfunction "-_2") (pintype "passive"))
      (node (ref "LED4") (pin "K") (pinfunction "C_K") (pintype "passive"))
      (node (ref "TP19") (pin "TP") (pinfunction "PP_TP") (pintype "input"))
      (node (ref "X1") (pin "9") (pinfunction "9_9") (pintype "passive"))
    )
    (net (code "22") (name "Net-(2I-KL)") (class "Default")
      (node (ref "2") (pin "6") (pinfunction "KL_6") (pintype "passive"))
      (node (ref "R14") (pin "1") (pinfunction "1_1") (pintype "passive"))
      (node (ref "R7") (pin "1") (pinfunction "1_1") (pintype "passive"))
      (node (ref "TP21") (pin "TP") (pinfunction "PP_TP") (pintype "input"))
    )
    (net (code "23") (name "Net-(2J-KL)") (class "Default")
      (node (ref "2") (pin "7") (pinfunction "KL_7") (pintype "passive"))
      (node (ref "LED6") (pin "A") (pinfunction "A_A") (pintype "passive"))
      (node (ref "TP22") (pin "TP") (pinfunction "PP_TP") (pintype "input"))
      (node (ref "X1") (pin "8") (pinfunction "8_8") (pintype "passive"))
    )
    (net (code "24") (name "Net-(2K-KL)") (class "Default")
      (node (ref "2") (pin "8") (pinfunction "KL_8") (pintype "passive"))
      (node (ref "D14") (pin "2") (pinfunction "-_2") (pintype "passive"))
      (node (ref "LED7") (pin "K") (pinfunction "C_K") (pintype "passive"))
      (node (ref "TP23") (pin "TP") (pinfunction "PP_TP") (pintype "input"))
      (node (ref "X1") (pin "14") (pinfunction "14_14") (pintype "passive"))
    )
    (net (code "25") (name "Net-(2L-KL)") (class "Default")
      (node (ref "2") (pin "9") (pinfunction "KL_9") (pintype "passive"))
      (node (ref "D12") (pin "1") (pinfunction "+_1") (pintype "passive"))
      (node (ref "D14") (pin "1") (pinfunction "+_1") (pintype "passive"))
      (node (ref "D2") (pin "1") (pinfunction "+_1") (pintype "passive"))
      (node (ref "JP5") (pin "2") (pinfunction "2_2") (pintype "passive"))
      (node (ref "JP6") (pin "1") (pinfunction "1_1") (pintype "passive"))
      (node (ref "JP6") (pin "2") (pinfunction "2_2") (pintype "passive"))
      (node (ref "TP24") (pin "TP") (pinfunction "PP_TP") (pintype "input"))
    )
    (net (code "26") (name "Net-(C2-Pad1)") (class "Default")
      (node (ref "C2") (pin "1") (pinfunction "1_1") (pintype "passive"))
      (node (ref "R10") (pin "1") (pinfunction "1_1") (pintype "passive"))
      (node (ref "R12") (pin "2") (pinfunction "2_2") (pintype "passive"))
    )
    (net (code "27") (name "Net-(D1-+)") (class "Default")
      (node (ref "D1") (pin "1") (pinfunction "+_1") (pintype "passive"))
      (node (ref "R27") (pin "1") (pinfunction "1_1") (pintype "passive"))
    )
    (net (code "28") (name "Net-(D3-+)") (class "Default")
      (node (ref "D3") (pin "1") (pinfunction "+_1") (pintype "passive"))
      (node (ref "R33") (pin "1") (pinfunction "1_1") (pintype "passive"))
    )
    (net (code "29") (name "Net-(D3--)") (class "Default")
      (node (ref "C1") (pin "2") (pinfunction "2_2") (pintype "passive"))
      (node (ref "D3") (pin "2") (pinfunction "-_2") (pintype "passive"))
      (node (ref "IC5") (pin "2") (pinfunction "TR_2") (pintype "input"))
      (node (ref "IC5") (pin "6") (pinfunction "THR_6") (pintype "input"))
      (node (ref "R24") (pin "1") (pinfunction "1_1") (pintype "passive"))
    )
    (net (code "30") (name "Net-(D8-+)") (class "Default")
      (node (ref "D8") (pin "1") (pinfunction "+_1") (pintype "passive"))
      (node (ref "R17") (pin "1") (pinfunction "1_1") (pintype "passive"))
    )
    (net (code "31") (name "Net-(D8--)") (class "Default")
      (node (ref "D8") (pin "2") (pinfunction "-_2") (pintype "passive"))
      (node (ref "IC7") (pin "2") (pinfunction "OUT_2") (pintype "open_collector"))
      (node (ref "Q10") (pin "1") (pinfunction "G_1") (pintype "passive"))
      (node (ref "R22") (pin "2") (pinfunction "2_2") (pintype "passive"))
    )
    (net (code "32") (name "Net-(D13-+)") (class "Default")
      (node (ref "D13") (pin "1") (pinfunction "+_1") (pintype "passive"))
      (node (ref "JP5") (pin "1") (pinfunction "1_1") (pintype "passive"))
    )
    (net (code "33") (name "Net-(D15--)") (class "Default")
      (node (ref "D15") (pin "2") (pinfunction "-_2") (pintype "passive"))
      (node (ref "Q1") (pin "2") (pinfunction "C_2") (pintype "passive"))
      (node (ref "Q3") (pin "2") (pinfunction "C_2") (pintype "passive"))
      (node (ref "X1") (pin "5") (pinfunction "5_5") (pintype "passive"))
    )
    (net (code "34") (name "Net-(IC3A-A)") (class "Default")
      (node (ref "IC3") (pin "10") (pinfunction "A_10") (pintype "input"))
      (node (ref "R31") (pin "1") (pinfunction "1_1") (pintype "passive"))
      (node (ref "X1") (pin "4") (pinfunction "4_4") (pintype "passive"))
      (node (ref "X3") (pin "2") (pinfunction "S_2") (pintype "passive"))
    )
    (net (code "35") (name "Net-(IC3A-B)") (class "Default")
      (node (ref "IC3") (pin "13") (pinfunction "B_13") (pintype "input"))
      (node (ref "R30") (pin "1") (pinfunction "1_1") (pintype "passive"))
      (node (ref "X1") (pin "3") (pinfunction "3_3") (pintype "passive"))
      (node (ref "X3") (pin "3") (pinfunction "S_3") (pintype "passive"))
    )
    (net (code "36") (name "Net-(IC3A-C)") (class "Default")
      (node (ref "IC3") (pin "12") (pinfunction "C_12") (pintype "input"))
      (node (ref "R29") (pin "1") (pinfunction "1_1") (pintype "passive"))
      (node (ref "X1") (pin "2") (pinfunction "2_2") (pintype "passive"))
      (node (ref "X3") (pin "4") (pinfunction "S_4") (pintype "passive"))
    )
    (net (code "37") (name "Net-(IC3A-Q0)") (class "Default")
      (node (ref "IC3") (pin "3") (pinfunction "Q0_3") (pintype "output"))
      (node (ref "IC6") (pin "1") (pinfunction "I1_1") (pintype "input"))
      (node (ref "IC6") (pin "2") (pinfunction "I2_2") (pintype "input"))
      (node (ref "Q11") (pin "1") (pinfunction "G_1") (pintype "passive"))
    )
    (net (code "38") (name "Net-(IC3A-Q1)") (class "Default")
      (node (ref "IC3") (pin "14") (pinfunction "Q1_14") (pintype "output"))
      (node (ref "IC6") (pin "6") (pinfunction "I6_6") (pintype "input"))
    )
    (net (code "39") (name "Net-(IC3A-Q2)") (class "Default")
      (node (ref "IC3") (pin "2") (pinfunction "Q2_2") (pintype "output"))
      (node (ref "IC6") (pin "7") (pinfunction "I7_7") (pintype "input"))
    )
    (net (code "40") (name "Net-(IC3A-Q3)") (class "Default")
      (node (ref "IC3") (pin "15") (pinfunction "Q3_15") (pintype "output"))
      (node (ref "IC6") (pin "5") (pinfunction "I5_5") (pintype "input"))
    )
    (net (code "41") (name "Net-(IC3A-Q4)") (class "Default")
      (node (ref "IC3") (pin "1") (pinfunction "Q4_1") (pintype "output"))
      (node (ref "IC6") (pin "4") (pinfunction "I4_4") (pintype "input"))
    )
    (net (code "42") (name "Net-(IC3A-Q5)") (class "Default")
      (node (ref "IC3") (pin "6") (pinfunction "Q5_6") (pintype "output"))
      (node (ref "IC6") (pin "3") (pinfunction "I3_3") (pintype "input"))
    )
    (net (code "43") (name "Net-(IC4-ADJ)") (class "Default")
      (node (ref "IC4") (pin "1") (pinfunction "ADJ_1") (pintype "input"))
      (node (ref "R18") (pin "1") (pinfunction "1_1") (pintype "passive"))
      (node (ref "R5") (pin "2") (pinfunction "2_2") (pintype "passive"))
      (node (ref "X1") (pin "7") (pinfunction "7_7") (pintype "passive"))
    )
    (net (code "44") (name "Net-(IC4-VI)") (class "Default")
      (node (ref "IC4") (pin "3") (pinfunction "VI_3") (pintype "input"))
      (node (ref "Q2") (pin "2") (pinfunction "C_2") (pintype "passive"))
      (node (ref "Q4") (pin "2") (pinfunction "C_2") (pintype "passive"))
    )
    (net (code "45") (name "Net-(IC4-VO)") (class "Default")
      (node (ref "IC4") (pin "2") (pinfunction "VO_2") (pintype "passive"))
      (node (ref "R18") (pin "2") (pinfunction "2_2") (pintype "passive"))
    )
    (net (code "46") (name "Net-(IC5-CV)") (class "Default")
      (node (ref "IC5") (pin "5") (pinfunction "CV_5") (pintype "input"))
      (node (ref "R26") (pin "2") (pinfunction "2_2") (pintype "passive"))
    )
    (net (code "47") (name "Net-(IC5-Q)") (class "Default")
      (node (ref "IC5") (pin "3") (pinfunction "Q_3") (pintype "output"))
      (node (ref "IC8") (pin "12") (pinfunction "A_12") (pintype "input"))
      (node (ref "R26") (pin "1") (pinfunction "1_1") (pintype "passive"))
    )
    (net (code "48") (name "Net-(IC6-O2)") (class "Default")
      (node (ref "IC6") (pin "15") (pinfunction "O2_15") (pintype "open_collector"))
      (node (ref "R13") (pin "1") (pinfunction "1_1") (pintype "passive"))
    )
    (net (code "49") (name "Net-(IC7A-+IN)") (class "Default")
      (node (ref "IC7") (pin "5") (pinfunction "+IN_5") (pintype "input"))
      (node (ref "R15") (pin "1") (pinfunction "1_1") (pintype "passive"))
      (node (ref "R16") (pin "2") (pinfunction "2_2") (pintype "passive"))
      (node (ref "R17") (pin "2") (pinfunction "2_2") (pintype "passive"))
    )
    (net (code "50") (name "Net-(IC7A--IN)") (class "Default")
      (node (ref "C3") (pin "1") (pinfunction "1_1") (pintype "passive"))
      (node (ref "IC7") (pin "4") (pinfunction "-IN_4") (pintype "input"))
      (node (ref "R12") (pin "1") (pinfunction "1_1") (pintype "passive"))
    )
    (net (code "51") (name "Net-(IC7B-+IN)") (class "Default")
      (node (ref "IC7") (pin "7") (pinfunction "+IN_7") (pintype "input"))
      (node (ref "R25") (pin "1") (pinfunction "1_1") (pintype "passive"))
      (node (ref "R6") (pin "1") (pinfunction "1_1") (pintype "passive"))
    )
    (net (code "52") (name "Net-(IC7B--IN)") (class "Default")
      (node (ref "IC7") (pin "6") (pinfunction "-IN_6") (pintype "input"))
      (node (ref "IC7") (pin "8") (pinfunction "-IN_8") (pintype "input"))
      (node (ref "R5") (pin "1") (pinfunction "1_1") (pintype "passive"))
    )
    (net (code "53") (name "Net-(IC7B-OUT)") (class "Default")
      (node (ref "IC7") (pin "1") (pinfunction "OUT_1") (pintype "open_collector"))
      (node (ref "R10") (pin "2") (pinfunction "2_2") (pintype "passive"))
      (node (ref "R19") (pin "2") (pinfunction "2_2") (pintype "passive"))
    )
    (net (code "54") (name "Net-(IC7C-+IN)") (class "Default")
      (node (ref "C5") (pin "1") (pinfunction "1_1") (pintype "passive"))
      (node (ref "IC7") (pin "9") (pinfunction "+IN_9") (pintype "input"))
      (node (ref "R25") (pin "2") (pinfunction "2_2") (pintype "passive"))
      (node (ref "R8") (pin "2") (pinfunction "2_2") (pintype "passive"))
    )
    (net (code "55") (name "Net-(IC7C-OUT)") (class "Default")
      (node (ref "C9") (pin "2") (pinfunction "2_2") (pintype "passive"))
      (node (ref "IC7") (pin "14") (pinfunction "OUT_14") (pintype "open_collector"))
      (node (ref "R9") (pin "2") (pinfunction "2_2") (pintype "passive"))
    )
    (net (code "56") (name "Net-(IC7D-+IN)") (class "Default")
      (node (ref "C8") (pin "1") (pinfunction "1_1") (pintype "passive"))
      (node (ref "IC7") (pin "11") (pinfunction "+IN_11") (pintype "input"))
      (node (ref "R1") (pin "1") (pinfunction "1_1") (pintype "passive"))
    )
    (net (code "57") (name "Net-(IC7D--IN)") (class "Default")
      (node (ref "IC7") (pin "10") (pinfunction "-IN_10") (pintype "input"))
      (node (ref "R2") (pin "2") (pinfunction "2_2") (pintype "passive"))
    )
    (net (code "58") (name "Net-(IC7D-OUT)") (class "Default")
      (node (ref "IC7") (pin "13") (pinfunction "OUT_13") (pintype "open_collector"))
      (node (ref "Q9") (pin "1") (pinfunction "B_1") (pintype "passive"))
      (node (ref "R32") (pin "2") (pinfunction "2_2") (pintype "passive"))
      (node (ref "T3") (pin "B") (pinfunction "B_B") (pintype "passive"))
    )
    (net (code "59") (name "Net-(IC8B-B)") (class "Default")
      (node (ref "IC8") (pin "11") (pinfunction "B_11") (pintype "input"))
      (node (ref "IC8") (pin "9") (pinfunction "~{Q}_9") (pintype "output"))
      (node (ref "R35") (pin "2") (pinfunction "2_2") (pintype "passive"))
    )
    (net (code "60") (name "Net-(IC8B-T2)") (class "Default")
      (node (ref "C10") (pin "1") (pinfunction "1_1") (pintype "passive"))
      (node (ref "IC8") (pin "14") (pinfunction "T2_14") (pintype "input"))
      (node (ref "R34") (pin "1") (pinfunction "1_1") (pintype "passive"))
    )
    (net (code "61") (name "Net-(JP1-Pad2)") (class "Default")
      (node (ref "JP1") (pin "2") (pinfunction "2_2") (pintype "passive"))
      (node (ref "R36") (pin "2") (pinfunction "2_2") (pintype "passive"))
      (node (ref "R37") (pin "2") (pinfunction "2_2") (pintype "passive"))
    )
    (net (code "62") (name "Net-(JP3-Pad1)") (class "Default")
      (node (ref "JP3") (pin "1") (pinfunction "1_1") (pintype "passive"))
      (node (ref "R23") (pin "2") (pinfunction "2_2") (pintype "passive"))
    )
    (net (code "63") (name "Net-(LED1-PadA)") (class "Default")
      (node (ref "LED1") (pin "A") (pinfunction "A_A") (pintype "passive"))
      (node (ref "LED2") (pin "A") (pinfunction "A_A") (pintype "passive"))
      (node (ref "LED3") (pin "A") (pinfunction "A_A") (pintype "passive"))
      (node (ref "LED4") (pin "A") (pinfunction "A_A") (pintype "passive"))
      (node (ref "LED7") (pin "A") (pinfunction "A_A") (pintype "passive"))
      (node (ref "R11") (pin "1") (pinfunction "1_1") (pintype "passive"))
    )
    (net (code "64") (name "Net-(LED6-C)") (class "Default")
      (node (ref "LED6") (pin "K") (pinfunction "C_K") (pintype "passive"))
      (node (ref "R4") (pin "1") (pinfunction "1_1") (pintype "passive"))
    )
    (net (code "65") (name "Net-(Q1-B)") (class "Default")
      (node (ref "Q1") (pin "1") (pinfunction "B_1") (pintype "passive"))
      (node (ref "Q3") (pin "1") (pinfunction "B_1") (pintype "passive"))
      (node (ref "R13") (pin "2") (pinfunction "2_2") (pintype "passive"))
    )
    (net (code "66") (name "Net-(Q2-B)") (class "Default")
      (node (ref "Q2") (pin "1") (pinfunction "B_1") (pintype "passive"))
      (node (ref "Q4") (pin "1") (pinfunction "B_1") (pintype "passive"))
      (node (ref "R9") (pin "1") (pinfunction "1_1") (pintype "passive"))
    )
    (net (code "67") (name "Net-(Q5-B)") (class "Default")
      (node (ref "Q5") (pin "1") (pinfunction "B_1") (pintype "passive"))
      (node (ref "Q6") (pin "1") (pinfunction "B_1") (pintype "passive"))
      (node (ref "Q6") (pin "2") (pinfunction "C_2") (pintype "passive"))
      (node (ref "Q7") (pin "1") (pinfunction "B_1") (pintype "passive"))
      (node (ref "Q7") (pin "2") (pinfunction "C_2") (pintype "passive"))
      (node (ref "Q8") (pin "1") (pinfunction "B_1") (pintype "passive"))
      (node (ref "R38") (pin "1") (pinfunction "1_1") (pintype "passive"))
      (node (ref "R39") (pin "1") (pinfunction "1_1") (pintype "passive"))
      (node (ref "T1") (pin "2") (pinfunction "B_2") (pintype "passive"))
      (node (ref "T1") (pin "4") (pinfunction "B_4") (pintype "passive"))
      (node (ref "T1") (pin "6") (pinfunction "C1_6") (pintype "passive"))
      (node (ref "X2") (pin "2") (pinfunction "S_2") (pintype "passive"))
    )
    (net (code "68") (name "Net-(Q5-E)") (class "Default")
      (node (ref "Q5") (pin "3") (pinfunction "E_3") (pintype "passive"))
      (node (ref "Q8") (pin "3") (pinfunction "E_3") (pintype "passive"))
      (node (ref "R21") (pin "2") (pinfunction "2_2") (pintype "passive"))
      (node (ref "T1") (pin "1") (pinfunction "E_1") (pintype "passive"))
    )
    (net (code "69") (name "Net-(Q6-E)") (class "Default")
      (node (ref "Q6") (pin "3") (pinfunction "E_3") (pintype "passive"))
      (node (ref "Q7") (pin "3") (pinfunction "E_3") (pintype "passive"))
      (node (ref "R20") (pin "2") (pinfunction "2_2") (pintype "passive"))
      (node (ref "T1") (pin "3") (pinfunction "E_3") (pintype "passive"))
    )
    (net (code "70") (name "Net-(Q9-C)") (class "Default")
      (node (ref "Q9") (pin "2") (pinfunction "C_2") (pintype "passive"))
      (node (ref "R3") (pin "2") (pinfunction "2_2") (pintype "passive"))
      (node (ref "T3") (pin "C") (pinfunction "C_C") (pintype "passive"))
      (node (ref "X1") (pin "21") (pinfunction "21_21") (pintype "passive"))
    )
    (net (code "71") (name "Net-(Q10-D)") (class "Default")
      (node (ref "Q10") (pin "3") (pinfunction "D_3") (pintype "passive"))
      (node (ref "R7") (pin "2") (pinfunction "2_2") (pintype "passive"))
    )
    (net (code "72") (name "Net-(R1-Pad2)") (class "Default")
      (node (ref "R1") (pin "2") (pinfunction "2_2") (pintype "passive"))
      (node (ref "X1") (pin "22") (pinfunction "22_22") (pintype "passive"))
    )
    (net (code "73") (name "Net-(R27-Pad2)") (class "Default")
      (node (ref "R27") (pin "2") (pinfunction "2_2") (pintype "passive"))
      (node (ref "R28") (pin "1") (pinfunction "1_1") (pintype "passive"))
    )
    (net (code "74") (name "Net-(R33-Pad2)") (class "Default")
      (node (ref "R33") (pin "2") (pinfunction "2_2") (pintype "passive"))
      (node (ref "X1") (pin "16") (pinfunction "16_16") (pintype "passive"))
    )
    (net (code "75") (name "Net-(TACHO_BEL-PP)") (class "Default")
      (node (ref "TACHO_BEL") (pin "TP") (pinfunction "PP_TP") (pintype "input"))
      (node (ref "X1") (pin "24") (pinfunction "24_24") (pintype "passive"))
    )
    (net (code "76") (name "VCC") (class "Default")
      (node (ref "6V") (pin "TP") (pinfunction "PP_TP") (pintype "input"))
      (node (ref "C4") (pin "1") (pinfunction "1_1") (pintype "passive"))
      (node (ref "IC1") (pin "OUT") (pinfunction "OUT_OUT") (pintype "passive"))
      (node (ref "IC2") (pin "1") (pinfunction "OUT_1") (pintype "passive"))
      (node (ref "IC7") (pin "3") (pinfunction "V+_3") (pintype "power_in"))
      (node (ref "R11") (pin "2") (pinfunction "2_2") (pintype "passive"))
      (node (ref "R15") (pin "2") (pinfunction "2_2") (pintype "passive"))
      (node (ref "R19") (pin "1") (pinfunction "1_1") (pintype "passive"))
      (node (ref "R6") (pin "2") (pinfunction "2_2") (pintype "passive"))
    )
    (net (code "77") (name "unconnected-(IC3A-Q6-Pad7)") (class "Default")
      (node (ref "IC3") (pin "7") (pinfunction "Q6_7") (pintype "output"))
    )
    (net (code "78") (name "unconnected-(IC3A-Q7-Pad4)") (class "Default")
      (node (ref "IC3") (pin "4") (pinfunction "Q7_4") (pintype "output"))
    )
    (net (code "79") (name "unconnected-(IC3A-Q8-Pad9)") (class "Default")
      (node (ref "IC3") (pin "9") (pinfunction "Q8_9") (pintype "output"))
    )
    (net (code "80") (name "unconnected-(IC3A-Q9-Pad5)") (class "Default")
      (node (ref "IC3") (pin "5") (pinfunction "Q9_5") (pintype "output"))
    )
    (net (code "81") (name "unconnected-(IC5-DIS-Pad7)") (class "Default")
      (node (ref "IC5") (pin "7") (pinfunction "DIS_7") (pintype "input"))
    )
    (net (code "82") (name "unconnected-(IC6-CD+-Pad9)") (class "Default")
      (node (ref "IC6") (pin "9") (pinfunction "CD+_9") (pintype "passive"))
    )
    (net (code "83") (name "unconnected-(IC8A-Q-Pad6)") (class "Default")
      (node (ref "IC8") (pin "6") (pinfunction "Q_6") (pintype "output"))
    )
    (net (code "84") (name "unconnected-(IC8A-T2-Pad2)") (class "Default")
      (node (ref "IC8") (pin "2") (pinfunction "T2_2") (pintype "input"))
    )
    (net (code "85") (name "unconnected-(IC8A-~{Q}-Pad7)") (class "Default")
      (node (ref "IC8") (pin "7") (pinfunction "~{Q}_7") (pintype "output"))
    )
    (net (code "86") (name "unconnected-(IC8B-Q-Pad10)") (class "Default")
      (node (ref "IC8") (pin "10") (pinfunction "Q_10") (pintype "output"))
    )
    (net (code "87") (name "unconnected-(Q3-C{slash}-Pad4)") (class "Default")
      (node (ref "Q3") (pin "4") (pinfunction "C/_4") (pintype "passive"))
    )
    (net (code "88") (name "unconnected-(Q4-C{slash}-Pad4)") (class "Default")
      (node (ref "Q4") (pin "4") (pinfunction "C/_4") (pintype "passive"))
    )
    (net (code "89") (name "unconnected-(Q5-C{slash}-Pad4)") (class "Default")
      (node (ref "Q5") (pin "4") (pinfunction "C/_4") (pintype "passive"))
    )
    (net (code "90") (name "unconnected-(Q6-C{slash}-Pad4)") (class "Default")
      (node (ref "Q6") (pin "4") (pinfunction "C/_4") (pintype "passive"))
    )
    (net (code "91") (name "unconnected-(T1A-C-Pad5)") (class "Default")
      (node (ref "T1") (pin "5") (pinfunction "C_5") (pintype "passive"))
    )
    (net (code "92") (name "unconnected-(T1B-C-Pad7)") (class "Default")
      (node (ref "T1") (pin "7") (pinfunction "C_7") (pintype "passive"))
    )
    (net (code "93") (name "unconnected-(X1-Pad20)") (class "Default")
      (node (ref "X1") (pin "20") (pinfunction "20_20") (pintype "passive"))
    )
  )
)
